# mp3431-boost-tester-mk-1_0_1.net
KiCad netlist of a schematic drawn in EAGLE
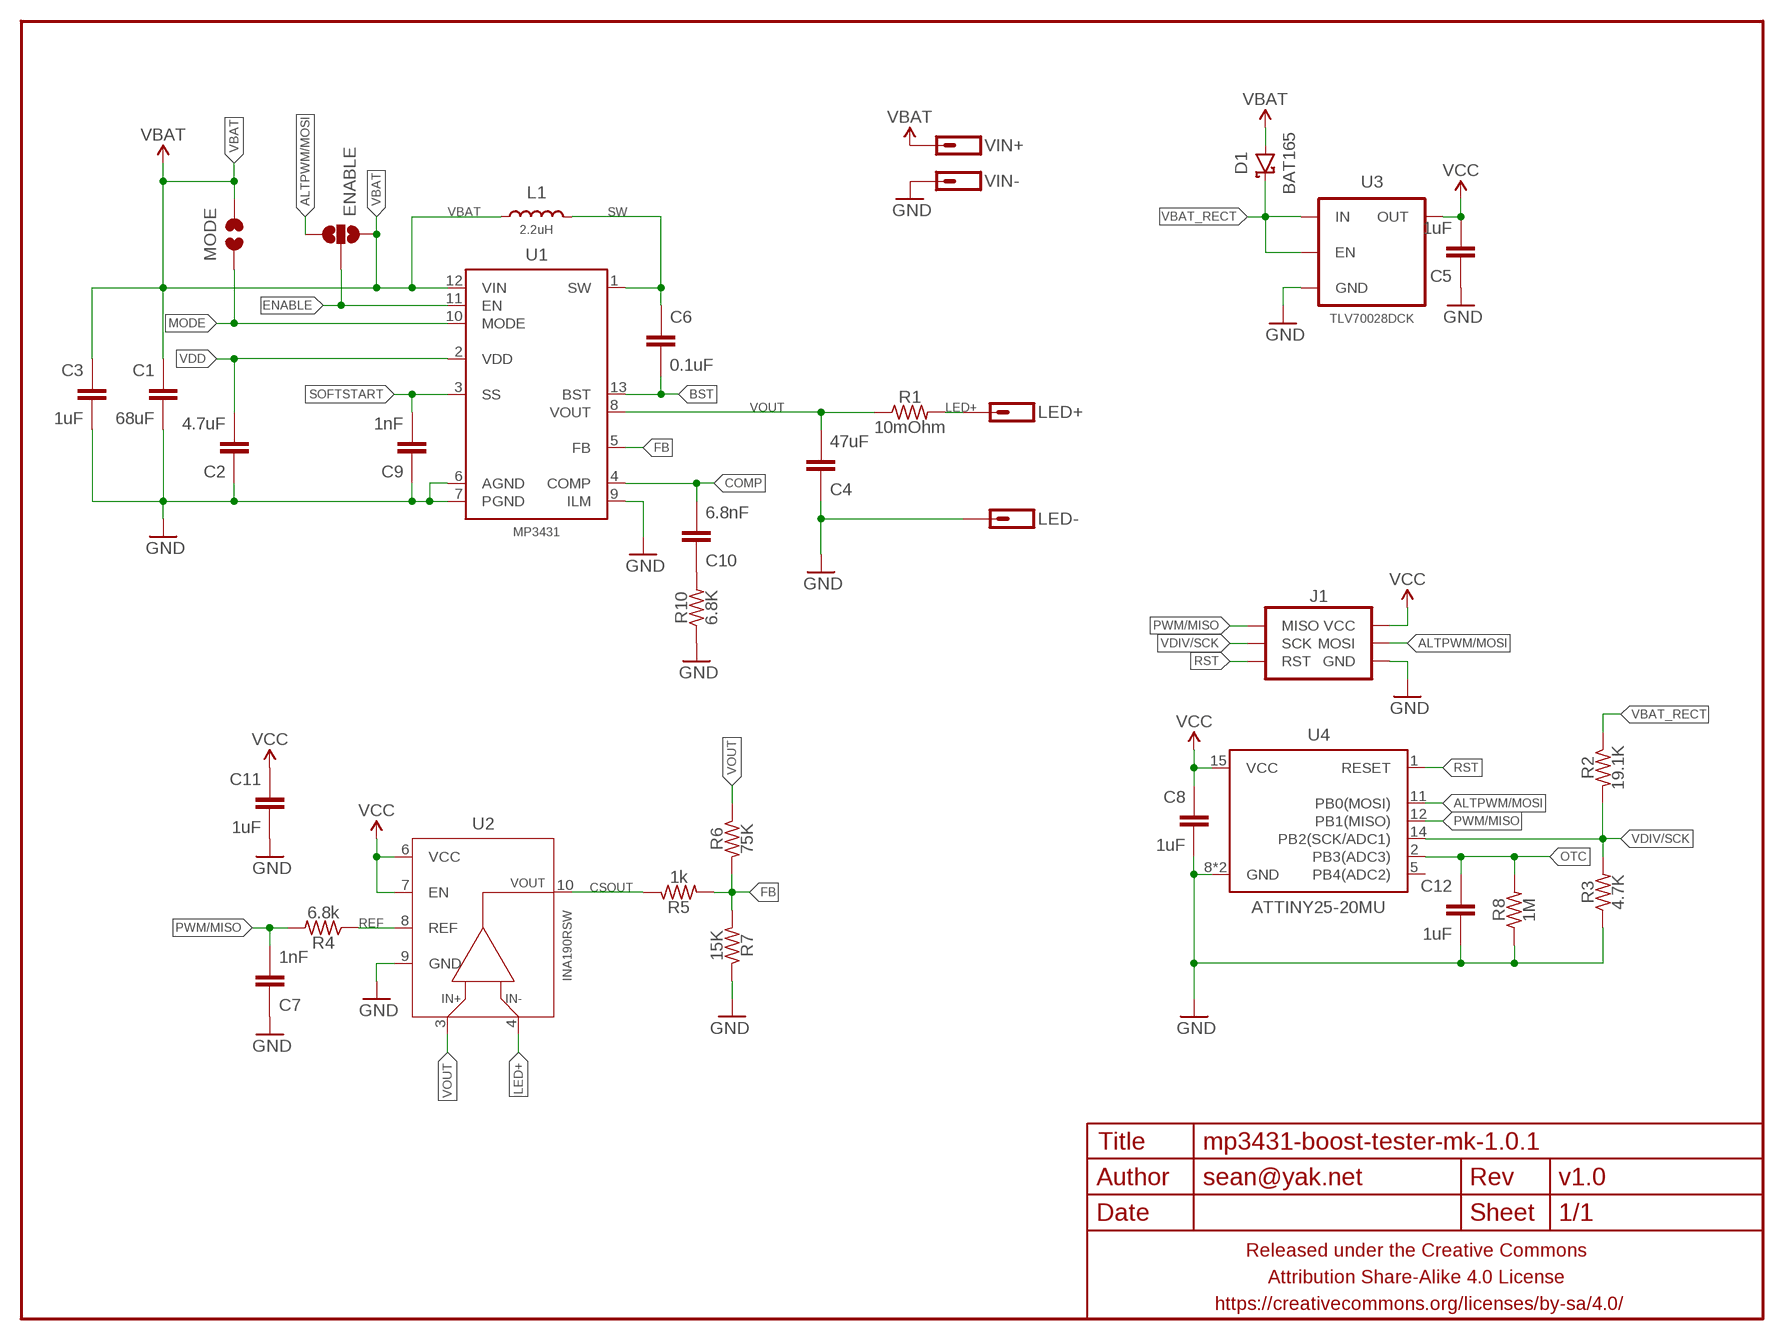
[diagram p0: schematic, sheet 1]

(export (version "E")
  (design (tool "Eeschema 10.0.6"))
  (components
    (comp (ref "C1")
      (value "68uF")
      (footprint "eagle-import:C1210")
      (libsource (lib "eagle-import") (part "CAPACITOR-CERAMICC1210"))
    )
    (comp (ref "C2")
      (value "4.7uF")
      (footprint "eagle-import:C0402")
      (libsource (lib "eagle-import") (part "CAPACITOR-CERAMICC0402"))
    )
    (comp (ref "C3")
      (value "1uF")
      (footprint "eagle-import:C0402")
      (libsource (lib "eagle-import") (part "CAPACITOR-CERAMICC0402"))
    )
    (comp (ref "C4")
      (value "47uF")
      (footprint "eagle-import:C1210")
      (libsource (lib "eagle-import") (part "CAPACITOR-CERAMICC1210"))
    )
    (comp (ref "C5")
      (value "1uF")
      (footprint "eagle-import:C0402")
      (libsource (lib "eagle-import") (part "CAPACITOR-CERAMICC0402"))
    )
    (comp (ref "C6")
      (value "0.1uF")
      (footprint "eagle-import:C0402")
      (libsource (lib "eagle-import") (part "CAPACITOR-CERAMICC0402"))
    )
    (comp (ref "C7")
      (value "1nF")
      (footprint "eagle-import:C0402")
      (libsource (lib "eagle-import") (part "CAPACITOR-CERAMICC0402"))
    )
    (comp (ref "C8")
      (value "1uF")
      (footprint "eagle-import:C0402")
      (libsource (lib "eagle-import") (part "CAPACITOR-CERAMICC0402"))
    )
    (comp (ref "C9")
      (value "1nF")
      (footprint "eagle-import:C0402")
      (libsource (lib "eagle-import") (part "CAPACITOR-CERAMICC0402"))
    )
    (comp (ref "C10")
      (value "6.8nF")
      (footprint "eagle-import:C0402")
      (libsource (lib "eagle-import") (part "CAPACITOR-CERAMICC0402"))
    )
    (comp (ref "C11")
      (value "1uF")
      (footprint "eagle-import:C0402")
      (libsource (lib "eagle-import") (part "CAPACITOR-CERAMICC0402"))
    )
    (comp (ref "C12")
      (value "1uF")
      (footprint "eagle-import:C0402")
      (libsource (lib "eagle-import") (part "CAPACITOR-CERAMICC0402"))
    )
    (comp (ref "D1")
      (value "BAT165")
      (footprint "eagle-import:SOD323-SCHOTTKY")
      (libsource (lib "eagle-import") (part "DIODE-SCHOTTKYSOD323"))
    )
    (comp (ref "ENABLE")
      (value "JUMPER-PAD-3-NOSMALL_BOX_SILK")
      (footprint "eagle-import:PAD-JUMPER-3-NO_YES_SILK_SMALL_BOX")
      (libsource (lib "eagle-import") (part "JUMPER-PAD-3-NOSMALL_BOX_SILK"))
    )
    (comp (ref "FRAME1")
      (value "FRAME-LETTERNO_PACKAGE")
      (footprint "eagle-import:DUMMY")
      (fields
        (field (name "DESIGNER") "sean@yak.net")
        (field (name "VERSION") "v1.0")
        (field (name "DESIGNER_1") "sean@yak.net")
        (field (name "VERSION_1") "v1.0")
      )
      (libsource (lib "eagle-import") (part "FRAME-LETTERNO_PACKAGE"))
    )
    (comp (ref "J1")
      (value "AVR_SPI_PRG_6PTH")
      (footprint "eagle-import:2X3")
      (libsource (lib "eagle-import") (part "AVR_SPI_PRG_6PTH"))
    )
    (comp (ref "L1")
      (value "2.2uH")
      (footprint "eagle-import:XAL7070")
      (libsource (lib "eagle-import") (part "INDUCTORXAL7070"))
    )
    (comp (ref "LED+")
      (value "M01PTH-1.2MM-NS")
      (footprint "eagle-import:1X01-1.2MM-NS")
      (libsource (lib "eagle-import") (part "M01PTH-1.2MM-NS"))
    )
    (comp (ref "LED-")
      (value "M01PTH-1.2MM-NS")
      (footprint "eagle-import:1X01-1.2MM-NS")
      (libsource (lib "eagle-import") (part "M01PTH-1.2MM-NS"))
    )
    (comp (ref "MODE")
      (value "JUMPER-PAD-2-NOYES_SILK")
      (footprint "eagle-import:PAD-JUMPER-2-NO_YES_SILK")
      (libsource (lib "eagle-import") (part "JUMPER-PAD-2-NOYES_SILK"))
    )
    (comp (ref "R1")
      (value "10mOhm")
      (footprint "eagle-import:R1206")
      (libsource (lib "eagle-import") (part "RESISTORR1206"))
    )
    (comp (ref "R2")
      (value "19.1K")
      (footprint "eagle-import:R0402")
      (libsource (lib "eagle-import") (part "RESISTORR0402"))
    )
    (comp (ref "R3")
      (value "4.7K")
      (footprint "eagle-import:R0402")
      (libsource (lib "eagle-import") (part "RESISTORR0402"))
    )
    (comp (ref "R4")
      (value "6.8k")
      (footprint "eagle-import:R0402")
      (libsource (lib "eagle-import") (part "RESISTORR0402"))
    )
    (comp (ref "R5")
      (value "1k")
      (footprint "eagle-import:R0402")
      (libsource (lib "eagle-import") (part "RESISTORR0402"))
    )
    (comp (ref "R6")
      (value "75K")
      (footprint "eagle-import:R0402")
      (libsource (lib "eagle-import") (part "RESISTORR0402"))
    )
    (comp (ref "R7")
      (value "15K")
      (footprint "eagle-import:R0402")
      (libsource (lib "eagle-import") (part "RESISTORR0402"))
    )
    (comp (ref "R8")
      (value "1M")
      (footprint "eagle-import:R0402")
      (libsource (lib "eagle-import") (part "RESISTORR0402"))
    )
    (comp (ref "R10")
      (value "6.8K")
      (footprint "eagle-import:R0402")
      (libsource (lib "eagle-import") (part "RESISTORR0402"))
    )
    (comp (ref "U1")
      (value "MP3431")
      (footprint "eagle-import:MP3431")
      (libsource (lib "eagle-import") (part "MP3431"))
    )
    (comp (ref "U2")
      (value "INA190RSW")
      (footprint "eagle-import:UQFN-10")
      (libsource (lib "eagle-import") (part "INA190RSW"))
    )
    (comp (ref "U3")
      (value "TLV70028DCK")
      (footprint "eagle-import:SC70")
      (libsource (lib "eagle-import") (part "V_REG_ENTLV700XXDCR"))
    )
    (comp (ref "U4")
      (value "ATTINY25-20MU")
      (footprint "eagle-import:QFN20")
      (libsource (lib "eagle-import") (part "ATTINY45TINY85-20-QFN"))
    )
    (comp (ref "VIN+")
      (value "M01PTH-1.2MM-NS")
      (footprint "eagle-import:1X01-1.2MM-NS")
      (libsource (lib "eagle-import") (part "M01PTH-1.2MM-NS"))
    )
    (comp (ref "VIN-")
      (value "M01PTH-1.2MM-NS")
      (footprint "eagle-import:1X01-1.2MM-NS")
      (libsource (lib "eagle-import") (part "M01PTH-1.2MM-NS"))
    )
  )
  (nets
    (net (code "1") (name "/CSOUT") (class "Default")
      (node (ref "R5") (pin "1") (pinfunction "1_1") (pintype "passive"))
      (node (ref "U2") (pin "10") (pinfunction "OUT_10") (pintype "bidirectional"))
    )
    (net (code "2") (name "/REF") (class "Default")
      (node (ref "R4") (pin "1") (pinfunction "1_1") (pintype "passive"))
      (node (ref "U2") (pin "8") (pinfunction "REF_8") (pintype "bidirectional"))
    )
    (net (code "3") (name "/SW") (class "Default")
      (node (ref "C6") (pin "1") (pinfunction "1_1") (pintype "passive"))
      (node (ref "L1") (pin "P$2") (pinfunction "2_P$2") (pintype "passive"))
      (node (ref "U1") (pin "1") (pinfunction "SW_1") (pintype "bidirectional"))
    )
    (net (code "4") (name "ALTPWM{slash}MOSI") (class "Default")
      (node (ref "ENABLE") (pin "3") (pinfunction "3_3") (pintype "passive"))
      (node (ref "J1") (pin "4") (pinfunction "MOSI_4") (pintype "passive"))
      (node (ref "U4") (pin "11") (pinfunction "PB0(MOSI)_11") (pintype "bidirectional"))
    )
    (net (code "5") (name "BST") (class "Default")
      (node (ref "C6") (pin "2") (pinfunction "2_2") (pintype "passive"))
      (node (ref "U1") (pin "13") (pinfunction "BST_13") (pintype "bidirectional"))
    )
    (net (code "6") (name "COMP") (class "Default")
      (node (ref "C10") (pin "2") (pinfunction "2_2") (pintype "passive"))
      (node (ref "U1") (pin "4") (pinfunction "COMP_4") (pintype "bidirectional"))
    )
    (net (code "7") (name "ENABLE") (class "Default")
      (node (ref "ENABLE") (pin "2") (pinfunction "2_2") (pintype "passive"))
      (node (ref "U1") (pin "11") (pinfunction "EN_11") (pintype "bidirectional"))
    )
    (net (code "8") (name "FB") (class "Default")
      (node (ref "R5") (pin "2") (pinfunction "2_2") (pintype "passive"))
      (node (ref "R6") (pin "2") (pinfunction "2_2") (pintype "passive"))
      (node (ref "R7") (pin "2") (pinfunction "2_2") (pintype "passive"))
      (node (ref "U1") (pin "5") (pinfunction "FB_5") (pintype "bidirectional"))
    )
    (net (code "9") (name "GND") (class "Default")
      (node (ref "C1") (pin "2") (pinfunction "2_2") (pintype "passive"))
      (node (ref "C11") (pin "2") (pinfunction "2_2") (pintype "passive"))
      (node (ref "C12") (pin "2") (pinfunction "2_2") (pintype "passive"))
      (node (ref "C2") (pin "1") (pinfunction "1_1") (pintype "passive"))
      (node (ref "C3") (pin "2") (pinfunction "2_2") (pintype "passive"))
      (node (ref "C4") (pin "1") (pinfunction "1_1") (pintype "passive"))
      (node (ref "C5") (pin "1") (pinfunction "1_1") (pintype "passive"))
      (node (ref "C7") (pin "1") (pinfunction "1_1") (pintype "passive"))
      (node (ref "C8") (pin "2") (pinfunction "2_2") (pintype "passive"))
      (node (ref "C9") (pin "1") (pinfunction "1_1") (pintype "passive"))
      (node (ref "J1") (pin "6") (pinfunction "GND_6") (pintype "passive"))
      (node (ref "LED-") (pin "P$1") (pinfunction "1_P$1") (pintype "passive"))
      (node (ref "R10") (pin "1") (pinfunction "1_1") (pintype "passive"))
      (node (ref "R3") (pin "1") (pinfunction "1_1") (pintype "passive"))
      (node (ref "R7") (pin "1") (pinfunction "1_1") (pintype "passive"))
      (node (ref "R8") (pin "1") (pinfunction "1_1") (pintype "passive"))
      (node (ref "U1") (pin "6") (pinfunction "AGND_6") (pintype "bidirectional"))
      (node (ref "U1") (pin "7") (pinfunction "PGND_7") (pintype "bidirectional"))
      (node (ref "U1") (pin "9") (pinfunction "ILM_9") (pintype "bidirectional"))
      (node (ref "U2") (pin "9") (pinfunction "GND_9") (pintype "bidirectional"))
      (node (ref "U3") (pin "2") (pinfunction "GND_2") (pintype "input"))
      (node (ref "U4") (pin "8") (pinfunction "GND_8") (pintype "bidirectional"))
      (node (ref "U4") (pin "PAD") (pinfunction "GND_PAD") (pintype "bidirectional"))
      (node (ref "VIN-") (pin "P$1") (pinfunction "1_P$1") (pintype "passive"))
    )
    (net (code "10") (name "LED+") (class "Default")
      (node (ref "LED+") (pin "P$1") (pinfunction "1_P$1") (pintype "passive"))
      (node (ref "R1") (pin "2") (pinfunction "2_2") (pintype "passive"))
      (node (ref "U2") (pin "4") (pinfunction "VIN-_4") (pintype "bidirectional"))
    )
    (net (code "11") (name "MODE") (class "Default")
      (node (ref "MODE") (pin "1") (pinfunction "1_1") (pintype "passive"))
      (node (ref "U1") (pin "10") (pinfunction "MODE_10") (pintype "bidirectional"))
    )
    (net (code "12") (name "Net-(C10-Pad1)") (class "Default")
      (node (ref "C10") (pin "1") (pinfunction "1_1") (pintype "passive"))
      (node (ref "R10") (pin "2") (pinfunction "2_2") (pintype "passive"))
    )
    (net (code "13") (name "OTC") (class "Default")
      (node (ref "C12") (pin "1") (pinfunction "1_1") (pintype "passive"))
      (node (ref "R8") (pin "2") (pinfunction "2_2") (pintype "passive"))
      (node (ref "U4") (pin "2") (pinfunction "PB3(ADC3)_2") (pintype "bidirectional"))
    )
    (net (code "14") (name "PWM{slash}MISO") (class "Default")
      (node (ref "C7") (pin "2") (pinfunction "2_2") (pintype "passive"))
      (node (ref "J1") (pin "1") (pinfunction "MISO_1") (pintype "passive"))
      (node (ref "R4") (pin "2") (pinfunction "2_2") (pintype "passive"))
      (node (ref "U4") (pin "12") (pinfunction "PB1(MISO)_12") (pintype "bidirectional"))
    )
    (net (code "15") (name "RST") (class "Default")
      (node (ref "J1") (pin "5") (pinfunction "RST_5") (pintype "passive"))
      (node (ref "U4") (pin "1") (pinfunction "RESET_1") (pintype "bidirectional"))
    )
    (net (code "16") (name "SOFTSTART") (class "Default")
      (node (ref "C9") (pin "2") (pinfunction "2_2") (pintype "passive"))
      (node (ref "U1") (pin "3") (pinfunction "SS_3") (pintype "bidirectional"))
    )
    (net (code "17") (name "VBAT") (class "Default")
      (node (ref "C1") (pin "1") (pinfunction "1_1") (pintype "passive"))
      (node (ref "C3") (pin "1") (pinfunction "1_1") (pintype "passive"))
      (node (ref "D1") (pin "A") (pinfunction "A_A") (pintype "passive"))
      (node (ref "ENABLE") (pin "1") (pinfunction "1_1") (pintype "passive"))
      (node (ref "L1") (pin "P$1") (pinfunction "1_P$1") (pintype "passive"))
      (node (ref "MODE") (pin "2") (pinfunction "2_2") (pintype "passive"))
      (node (ref "U1") (pin "12") (pinfunction "VIN_12") (pintype "bidirectional"))
      (node (ref "VIN+") (pin "P$1") (pinfunction "1_P$1") (pintype "passive"))
    )
    (net (code "18") (name "VBAT_RECT") (class "Default")
      (node (ref "D1") (pin "C") (pinfunction "C_C") (pintype "passive"))
      (node (ref "R2") (pin "1") (pinfunction "1_1") (pintype "passive"))
      (node (ref "U3") (pin "1") (pinfunction "IN_1") (pintype "input"))
      (node (ref "U3") (pin "3") (pinfunction "EN_3") (pintype "input"))
    )
    (net (code "19") (name "VCC") (class "Default")
      (node (ref "C11") (pin "1") (pinfunction "1_1") (pintype "passive"))
      (node (ref "C5") (pin "2") (pinfunction "2_2") (pintype "passive"))
      (node (ref "C8") (pin "1") (pinfunction "1_1") (pintype "passive"))
      (node (ref "J1") (pin "2") (pinfunction "VCC_2") (pintype "passive"))
      (node (ref "U2") (pin "6") (pinfunction "VCC_6") (pintype "bidirectional"))
      (node (ref "U2") (pin "7") (pinfunction "EN_7") (pintype "bidirectional"))
      (node (ref "U3") (pin "5") (pinfunction "OUT_5") (pintype "passive"))
      (node (ref "U4") (pin "15") (pinfunction "VCC_15") (pintype "bidirectional"))
    )
    (net (code "20") (name "VDD") (class "Default")
      (node (ref "C2") (pin "2") (pinfunction "2_2") (pintype "passive"))
      (node (ref "U1") (pin "2") (pinfunction "VDD_2") (pintype "bidirectional"))
    )
    (net (code "21") (name "VDIV{slash}SCK") (class "Default")
      (node (ref "J1") (pin "3") (pinfunction "SCK_3") (pintype "passive"))
      (node (ref "R2") (pin "2") (pinfunction "2_2") (pintype "passive"))
      (node (ref "R3") (pin "2") (pinfunction "2_2") (pintype "passive"))
      (node (ref "U4") (pin "14") (pinfunction "PB2(SCK/ADC1)_14") (pintype "bidirectional"))
    )
    (net (code "22") (name "VOUT") (class "Default")
      (node (ref "C4") (pin "2") (pinfunction "2_2") (pintype "passive"))
      (node (ref "R1") (pin "1") (pinfunction "1_1") (pintype "passive"))
      (node (ref "R6") (pin "1") (pinfunction "1_1") (pintype "passive"))
      (node (ref "U1") (pin "8") (pinfunction "VOUT_8") (pintype "bidirectional"))
      (node (ref "U2") (pin "3") (pinfunction "VIN+_3") (pintype "bidirectional"))
    )
    (net (code "23") (name "unconnected-(U4-PB4(ADC2)-Pad5)") (class "Default")
      (node (ref "U4") (pin "5") (pinfunction "PB4(ADC2)_5") (pintype "bidirectional"))
    )
  )
)
